# NinjaPCB-4x4-NinNin_ver2_0.net
KiCad netlist of a schematic drawn in EAGLE
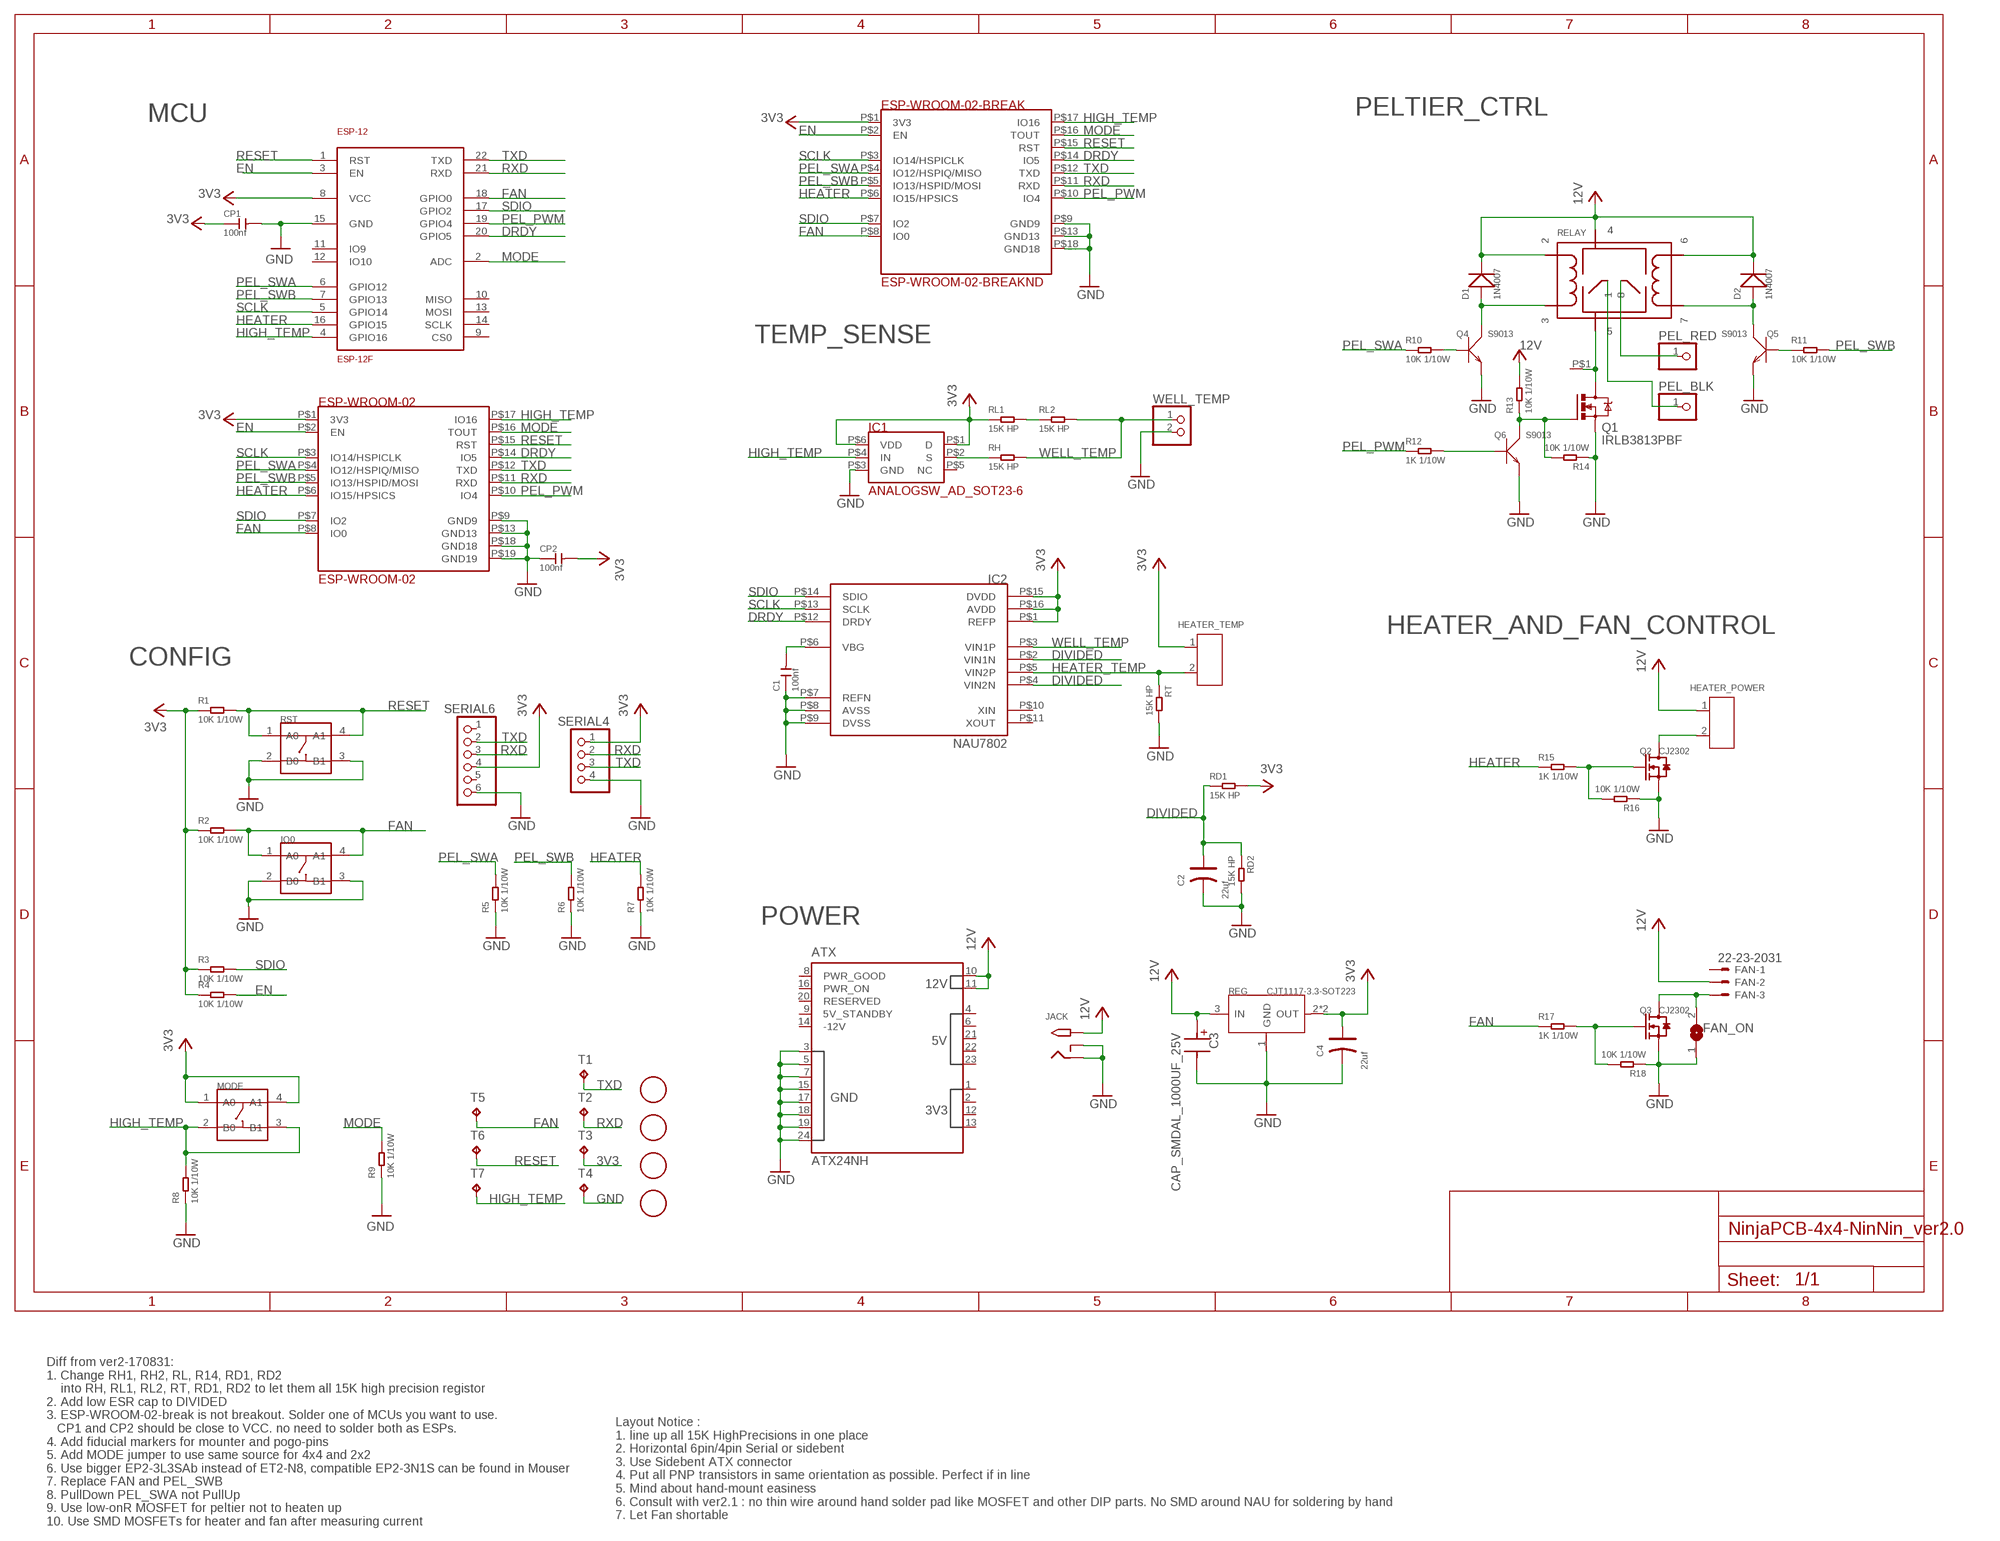
[diagram p0: schematic, sheet 1]

(export (version "E")
  (design (tool "Eeschema 10.0.6"))
  (components
    (comp (ref "ATX")
      (value "ATX24NH")
      (footprint "eagle-import:ATX24")
      (libsource (lib "eagle-import") (part "ATX24NH"))
    )
    (comp (ref "C1")
      (value "100nf")
      (footprint "eagle-import:C0603")
      (fields (field (name "MPN") "CC0603KRX7R9BB104"))
      (libsource (lib "eagle-import") (part "CERAMIC-100NF-50V-10%-X7R(0603)"))
    )
    (comp (ref "C2")
      (value "22uf")
      (footprint "eagle-import:AVX-B")
      (fields (field (name "MPN") "TAJB226*016#NJ"))
      (libsource (lib "eagle-import") (part "TANTALUM-SMD-22UF-16V(AVX-B)"))
    )
    (comp (ref "C3")
      (value "CAP_SMDAL_1000UF_25V")
      (footprint "eagle-import:CAP_SMD_AL_D125")
      (libsource (lib "eagle-import") (part "CAP_SMDAL_1000UF_25V"))
    )
    (comp (ref "C4")
      (value "22uf")
      (footprint "eagle-import:AVX-B")
      (fields (field (name "MPN") "TAJB226*016#NJ"))
      (libsource (lib "eagle-import") (part "TANTALUM-SMD-22UF-16V(AVX-B)"))
    )
    (comp (ref "CP1")
      (value "100nf")
      (footprint "eagle-import:C0603")
      (fields (field (name "MPN") "CC0603KRX7R9BB104"))
      (libsource (lib "eagle-import") (part "CERAMIC-100NF-50V-10%-X7R(0603)"))
    )
    (comp (ref "CP2")
      (value "100nf")
      (footprint "eagle-import:C0603")
      (fields (field (name "MPN") "CC0603KRX7R9BB104"))
      (libsource (lib "eagle-import") (part "CERAMIC-100NF-50V-10%-X7R(0603)"))
    )
    (comp (ref "D1")
      (value "1N4007")
      (footprint "eagle-import:DO-214AC")
      (libsource (lib "eagle-import") (part "DIODE-GEN-PURPOSE-1KV-1A(DO-214AC)"))
    )
    (comp (ref "D2")
      (value "1N4007")
      (footprint "eagle-import:DO-214AC")
      (libsource (lib "eagle-import") (part "DIODE-GEN-PURPOSE-1KV-1A(DO-214AC)"))
    )
    (comp (ref "ESP-12")
      (value "ESP-12F")
      (footprint "eagle-import:ESP-12F")
      (libsource (lib "eagle-import") (part "ESP-12F"))
    )
    (comp (ref "ESP-WROOM-02")
      (value "ESP-WROOM-02")
      (footprint "eagle-import:ESP-WROOM-02")
      (libsource (lib "eagle-import") (part "ESP-WROOM-02"))
    )
    (comp (ref "ESP-WROOM-02-BREAK")
      (value "ESP-WROOM-02-BREAKND")
      (footprint "eagle-import:ESP-WROOM-02-BREAK-NODETAIL")
      (libsource (lib "eagle-import") (part "ESP-WROOM-02-BREAKND"))
    )
    (comp (ref "FAN")
      (value "22-23-2031")
      (footprint "eagle-import:22-23-2031")
      (fields (field (name "MF") "MOLEX"))
      (libsource (lib "eagle-import") (part "22-23-2031"))
    )
    (comp (ref "FAN_ON")
      (value "SJ")
      (footprint "eagle-import:SJ")
      (libsource (lib "eagle-import") (part "SJ"))
    )
    (comp (ref "HEATER_POWER")
      (value "SCREW-TERMINAL-GREEN(2P-3.5)")
      (footprint "eagle-import:H2-3.5-7.0X7.0MM")
      (libsource (lib "eagle-import") (part "SCREW-TERMINAL-GREEN(2P-3.5)"))
    )
    (comp (ref "HEATER_TEMP")
      (value "SCREW-TERMINAL-GREEN(2P-3.5)")
      (footprint "eagle-import:H2-3.5-7.0X7.0MM")
      (libsource (lib "eagle-import") (part "SCREW-TERMINAL-GREEN(2P-3.5)"))
    )
    (comp (ref "HEATSINK")
      (value "HEAT111PB015")
      (footprint "eagle-import:HEAT11PB015")
      (libsource (lib "eagle-import") (part "HEAT111PB015"))
    )
    (comp (ref "IC1")
      (value "ANALOGSW_AD_SOT23-6")
      (footprint "eagle-import:SOT-23-6")
      (libsource (lib "eagle-import") (part "ANALOGSW_AD_SOT23-6"))
    )
    (comp (ref "IC2")
      (value "NAU7802")
      (footprint "eagle-import:SOP-16")
      (libsource (lib "eagle-import") (part "NAU7802"))
    )
    (comp (ref "IO0")
      (value "DIP-SWITCH-TACTILE-SPST-NO/TS-1109(4P-D6.0MM)'TS-1109'")
      (footprint "eagle-import:SW4-6.0X6.0X5.0MM")
      (libsource (lib "eagle-import") (part "DIP-SWITCH-TACTILE-SPST-NO/TS-1109(4P-D6.0MM)'TS-1109'"))
    )
    (comp (ref "JACK")
      (value "2.1MMJACKTHM")
      (footprint "eagle-import:PJ-102A")
      (libsource (lib "eagle-import") (part "2.1MMJACKTHM"))
    )
    (comp (ref "MODE")
      (value "DIP-SWITCH-TACTILE-SPST-NO/TS-1109(4P-D6.0MM)'TS-1109'")
      (footprint "eagle-import:SW4-6.0X6.0X5.0MM")
      (libsource (lib "eagle-import") (part "DIP-SWITCH-TACTILE-SPST-NO/TS-1109(4P-D6.0MM)'TS-1109'"))
    )
    (comp (ref "PEL_BLK")
      (value "PINHD-1X1L")
      (footprint "eagle-import:1X01LONG")
      (libsource (lib "eagle-import") (part "PINHD-1X1L"))
    )
    (comp (ref "PEL_RED")
      (value "PINHD-1X1L")
      (footprint "eagle-import:1X01LONG")
      (libsource (lib "eagle-import") (part "PINHD-1X1L"))
    )
    (comp (ref "Q1")
      (value "IRLB3813PBF")
      (footprint "eagle-import:TO220BV")
      (libsource (lib "eagle-import") (part "IRF520"))
    )
    (comp (ref "Q2")
      (value "CJ2302")
      (footprint "eagle-import:SOT-23")
      (libsource (lib "eagle-import") (part "SMD-MOSFET-N-CH-20V-2.1A-CJ2302(SOT-23)"))
    )
    (comp (ref "Q3")
      (value "CJ2302")
      (footprint "eagle-import:SOT-23")
      (libsource (lib "eagle-import") (part "SMD-MOSFET-N-CH-20V-2.1A-CJ2302(SOT-23)"))
    )
    (comp (ref "Q4")
      (value "S9013")
      (footprint "eagle-import:SOT-23")
      (libsource (lib "eagle-import") (part "SMD-TRANSISTORS-NPN-25V-500MA-S9013(SOT-23)"))
    )
    (comp (ref "Q5")
      (value "S9013")
      (footprint "eagle-import:SOT-23")
      (libsource (lib "eagle-import") (part "SMD-TRANSISTORS-NPN-25V-500MA-S9013(SOT-23)"))
    )
    (comp (ref "Q6")
      (value "S9013")
      (footprint "eagle-import:SOT-23")
      (libsource (lib "eagle-import") (part "SMD-TRANSISTORS-NPN-25V-500MA-S9013(SOT-23)"))
    )
    (comp (ref "R1")
      (value "10K 1/10W")
      (footprint "eagle-import:R0603")
      (fields (field (name "MPN") "RC0603JR-0710KL"))
      (libsource (lib "eagle-import") (part "SMD-RES-10K-5%-1/10W(0603)"))
    )
    (comp (ref "R2")
      (value "10K 1/10W")
      (footprint "eagle-import:R0603")
      (fields (field (name "MPN") "RC0603JR-0710KL"))
      (libsource (lib "eagle-import") (part "SMD-RES-10K-5%-1/10W(0603)"))
    )
    (comp (ref "R3")
      (value "10K 1/10W")
      (footprint "eagle-import:R0603")
      (fields (field (name "MPN") "RC0603JR-0710KL"))
      (libsource (lib "eagle-import") (part "SMD-RES-10K-5%-1/10W(0603)"))
    )
    (comp (ref "R4")
      (value "10K 1/10W")
      (footprint "eagle-import:R0603")
      (fields (field (name "MPN") "RC0603JR-0710KL"))
      (libsource (lib "eagle-import") (part "SMD-RES-10K-5%-1/10W(0603)"))
    )
    (comp (ref "R5")
      (value "10K 1/10W")
      (footprint "eagle-import:R0603")
      (fields (field (name "MPN") "RC0603JR-0710KL"))
      (libsource (lib "eagle-import") (part "SMD-RES-10K-5%-1/10W(0603)"))
    )
    (comp (ref "R6")
      (value "10K 1/10W")
      (footprint "eagle-import:R0603")
      (fields (field (name "MPN") "RC0603JR-0710KL"))
      (libsource (lib "eagle-import") (part "SMD-RES-10K-5%-1/10W(0603)"))
    )
    (comp (ref "R7")
      (value "10K 1/10W")
      (footprint "eagle-import:R0603")
      (fields (field (name "MPN") "RC0603JR-0710KL"))
      (libsource (lib "eagle-import") (part "SMD-RES-10K-5%-1/10W(0603)"))
    )
    (comp (ref "R8")
      (value "10K 1/10W")
      (footprint "eagle-import:R0603")
      (fields (field (name "MPN") "RC0603JR-0710KL"))
      (libsource (lib "eagle-import") (part "SMD-RES-10K-5%-1/10W(0603)"))
    )
    (comp (ref "R9")
      (value "10K 1/10W")
      (footprint "eagle-import:R0603")
      (fields (field (name "MPN") "RC0603JR-0710KL"))
      (libsource (lib "eagle-import") (part "SMD-RES-10K-5%-1/10W(0603)"))
    )
    (comp (ref "R10")
      (value "10K 1/10W")
      (footprint "eagle-import:R0603")
      (fields (field (name "MPN") "RC0603JR-0710KL"))
      (libsource (lib "eagle-import") (part "SMD-RES-10K-5%-1/10W(0603)"))
    )
    (comp (ref "R11")
      (value "10K 1/10W")
      (footprint "eagle-import:R0603")
      (fields (field (name "MPN") "RC0603JR-0710KL"))
      (libsource (lib "eagle-import") (part "SMD-RES-10K-5%-1/10W(0603)"))
    )
    (comp (ref "R12")
      (value "1K 1/10W")
      (footprint "eagle-import:R0603")
      (fields (field (name "MPN") "RC0603JR-071KL"))
      (libsource (lib "eagle-import") (part "SMD-RES-1K-5%-1/10W(0603)"))
    )
    (comp (ref "R13")
      (value "10K 1/10W")
      (footprint "eagle-import:R0603")
      (fields (field (name "MPN") "RC0603JR-0710KL"))
      (libsource (lib "eagle-import") (part "SMD-RES-10K-5%-1/10W(0603)"))
    )
    (comp (ref "R14")
      (value "10K 1/10W")
      (footprint "eagle-import:R0603")
      (fields (field (name "MPN") "RC0603JR-0710KL"))
      (libsource (lib "eagle-import") (part "SMD-RES-10K-5%-1/10W(0603)"))
    )
    (comp (ref "R15")
      (value "1K 1/10W")
      (footprint "eagle-import:R0603")
      (fields (field (name "MPN") "RC0603JR-071KL"))
      (libsource (lib "eagle-import") (part "SMD-RES-1K-5%-1/10W(0603)"))
    )
    (comp (ref "R16")
      (value "10K 1/10W")
      (footprint "eagle-import:R0603")
      (fields (field (name "MPN") "RC0603JR-0710KL"))
      (libsource (lib "eagle-import") (part "SMD-RES-10K-5%-1/10W(0603)"))
    )
    (comp (ref "R17")
      (value "1K 1/10W")
      (footprint "eagle-import:R0603")
      (fields (field (name "MPN") "RC0603JR-071KL"))
      (libsource (lib "eagle-import") (part "SMD-RES-1K-5%-1/10W(0603)"))
    )
    (comp (ref "R18")
      (value "10K 1/10W")
      (footprint "eagle-import:R0603")
      (fields (field (name "MPN") "RC0603JR-0710KL"))
      (libsource (lib "eagle-import") (part "SMD-RES-10K-5%-1/10W(0603)"))
    )
    (comp (ref "RD1")
      (value "15K HP")
      (footprint "eagle-import:R0603")
      (libsource (lib "eagle-import") (part "R0603"))
    )
    (comp (ref "RD2")
      (value "15K HP")
      (footprint "eagle-import:R0603")
      (libsource (lib "eagle-import") (part "R0603"))
    )
    (comp (ref "REG")
      (value "CJT1117-3.3-SOT223")
      (footprint "eagle-import:SOT-223")
      (fields (field (name "MPN") "CJT1117-3.3"))
      (libsource (lib "eagle-import") (part "PMIC-CJT1117-3.3(SOT223)"))
    )
    (comp (ref "RELAY")
      (value "NEC-RELAY2EP2")
      (footprint "eagle-import:NEC-EP2")
      (libsource (lib "eagle-import") (part "NEC-RELAY2EP2"))
    )
    (comp (ref "RH")
      (value "15K HP")
      (footprint "eagle-import:R0603")
      (libsource (lib "eagle-import") (part "R0603"))
    )
    (comp (ref "RL1")
      (value "15K HP")
      (footprint "eagle-import:R0603")
      (libsource (lib "eagle-import") (part "R0603"))
    )
    (comp (ref "RL2")
      (value "15K HP")
      (footprint "eagle-import:R0603")
      (libsource (lib "eagle-import") (part "R0603"))
    )
    (comp (ref "RST")
      (value "DIP-SWITCH-TACTILE-SPST-NO/TS-1109(4P-D6.0MM)'TS-1109'")
      (footprint "eagle-import:SW4-6.0X6.0X5.0MM")
      (libsource (lib "eagle-import") (part "DIP-SWITCH-TACTILE-SPST-NO/TS-1109(4P-D6.0MM)'TS-1109'"))
    )
    (comp (ref "RT")
      (value "15K HP")
      (footprint "eagle-import:R0603")
      (fields (field (name "MPN") "RC0603FR-072KL"))
      (libsource (lib "eagle-import") (part "SMD-RES-2K-1%-1/10W(0603)"))
    )
    (comp (ref "SERIAL4")
      (value "PINHD-1X4")
      (footprint "eagle-import:1X04")
      (libsource (lib "eagle-import") (part "PINHD-1X4"))
    )
    (comp (ref "SERIAL6")
      (value "PINHD-1X6")
      (footprint "eagle-import:1X06")
      (libsource (lib "eagle-import") (part "PINHD-1X6"))
    )
    (comp (ref "T1")
      (value "TPTP20R")
      (footprint "eagle-import:TP20R")
      (libsource (lib "eagle-import") (part "TPTP20R"))
    )
    (comp (ref "T2")
      (value "TPTP20R")
      (footprint "eagle-import:TP20R")
      (libsource (lib "eagle-import") (part "TPTP20R"))
    )
    (comp (ref "T3")
      (value "TPTP20R")
      (footprint "eagle-import:TP20R")
      (libsource (lib "eagle-import") (part "TPTP20R"))
    )
    (comp (ref "T4")
      (value "TPTP20R")
      (footprint "eagle-import:TP20R")
      (libsource (lib "eagle-import") (part "TPTP20R"))
    )
    (comp (ref "T5")
      (value "TPTP20R")
      (footprint "eagle-import:TP20R")
      (libsource (lib "eagle-import") (part "TPTP20R"))
    )
    (comp (ref "T6")
      (value "TPTP20R")
      (footprint "eagle-import:TP20R")
      (libsource (lib "eagle-import") (part "TPTP20R"))
    )
    (comp (ref "T7")
      (value "TPTP20R")
      (footprint "eagle-import:TP20R")
      (libsource (lib "eagle-import") (part "TPTP20R"))
    )
    (comp (ref "U$3")
      (value "FIDUCIAL")
      (footprint "eagle-import:FIDUCIAL_1MM")
      (libsource (lib "eagle-import") (part "FIDUCIAL"))
    )
    (comp (ref "U$4")
      (value "FIDUCIAL")
      (footprint "eagle-import:FIDUCIAL_1MM")
      (libsource (lib "eagle-import") (part "FIDUCIAL"))
    )
    (comp (ref "U$5")
      (value "FIDUCIAL")
      (footprint "eagle-import:FIDUCIAL_1MM")
      (libsource (lib "eagle-import") (part "FIDUCIAL"))
    )
    (comp (ref "U$6")
      (value "FIDUCIAL")
      (footprint "eagle-import:FIDUCIAL_1MM")
      (libsource (lib "eagle-import") (part "FIDUCIAL"))
    )
    (comp (ref "WELL_TEMP")
      (value "PINHD-1X2")
      (footprint "eagle-import:1X02")
      (libsource (lib "eagle-import") (part "PINHD-1X2"))
    )
  )
  (nets
    (net (code "1") (name "/DIVIDED") (class "Default")
      (node (ref "C2") (pin "+") (pinfunction "+_+") (pintype "passive"))
      (node (ref "IC2") (pin "P$2") (pinfunction "VIN1N_P$2") (pintype "bidirectional"))
      (node (ref "IC2") (pin "P$4") (pinfunction "VIN2N_P$4") (pintype "bidirectional"))
      (node (ref "RD1") (pin "1") (pinfunction "1_1") (pintype "passive"))
      (node (ref "RD2") (pin "1") (pinfunction "1_1") (pintype "passive"))
    )
    (net (code "2") (name "/DRDY") (class "Default")
      (node (ref "ESP-12") (pin "20") (pinfunction "GPIO5_20") (pintype "bidirectional"))
      (node (ref "ESP-WROOM-02") (pin "P$14") (pinfunction "IO5_P$14") (pintype "bidirectional"))
      (node (ref "ESP-WROOM-02-BREAK") (pin "P$14") (pinfunction "IO5_P$14") (pintype "bidirectional"))
      (node (ref "IC2") (pin "P$12") (pinfunction "DRDY_P$12") (pintype "bidirectional"))
    )
    (net (code "3") (name "/EN") (class "Default")
      (node (ref "ESP-12") (pin "3") (pinfunction "EN_3") (pintype "bidirectional"))
      (node (ref "ESP-WROOM-02") (pin "P$2") (pinfunction "EN_P$2") (pintype "bidirectional"))
      (node (ref "ESP-WROOM-02-BREAK") (pin "P$2") (pinfunction "EN_P$2") (pintype "bidirectional"))
      (node (ref "R4") (pin "2") (pinfunction "2_2") (pintype "passive"))
    )
    (net (code "4") (name "/FAN") (class "Default")
      (node (ref "ESP-12") (pin "18") (pinfunction "GPIO0_18") (pintype "bidirectional"))
      (node (ref "ESP-WROOM-02") (pin "P$8") (pinfunction "IO0_P$8") (pintype "bidirectional"))
      (node (ref "ESP-WROOM-02-BREAK") (pin "P$8") (pinfunction "IO0_P$8") (pintype "bidirectional"))
      (node (ref "IO0") (pin "1") (pinfunction "A0_1") (pintype "bidirectional"))
      (node (ref "IO0") (pin "4") (pinfunction "A1_4") (pintype "bidirectional"))
      (node (ref "R17") (pin "1") (pinfunction "1_1") (pintype "passive"))
      (node (ref "R2") (pin "2") (pinfunction "2_2") (pintype "passive"))
      (node (ref "T5") (pin "TP") (pinfunction "TP_TP") (pintype "input"))
    )
    (net (code "5") (name "/HEATER") (class "Default")
      (node (ref "ESP-12") (pin "16") (pinfunction "GPIO15_16") (pintype "bidirectional"))
      (node (ref "ESP-WROOM-02") (pin "P$6") (pinfunction "IO15/HPSICS_P$6") (pintype "bidirectional"))
      (node (ref "ESP-WROOM-02-BREAK") (pin "P$6") (pinfunction "IO15/HPSICS_P$6") (pintype "bidirectional"))
      (node (ref "R15") (pin "1") (pinfunction "1_1") (pintype "passive"))
      (node (ref "R7") (pin "2") (pinfunction "2_2") (pintype "passive"))
    )
    (net (code "6") (name "/HEATER_TEMP") (class "Default")
      (node (ref "HEATER_TEMP") (pin "2") (pinfunction "2_2") (pintype "bidirectional"))
      (node (ref "IC2") (pin "P$5") (pinfunction "VIN2P_P$5") (pintype "bidirectional"))
      (node (ref "RT") (pin "1") (pinfunction "1_1") (pintype "passive"))
    )
    (net (code "7") (name "/HIGH_TEMP") (class "Default")
      (node (ref "ESP-12") (pin "4") (pinfunction "GPIO16_4") (pintype "bidirectional"))
      (node (ref "ESP-WROOM-02") (pin "P$17") (pinfunction "IO16_P$17") (pintype "bidirectional"))
      (node (ref "ESP-WROOM-02-BREAK") (pin "P$17") (pinfunction "IO16_P$17") (pintype "bidirectional"))
      (node (ref "IC1") (pin "P$4") (pinfunction "IN_P$4") (pintype "bidirectional"))
      (node (ref "MODE") (pin "2") (pinfunction "B0_2") (pintype "bidirectional"))
      (node (ref "MODE") (pin "3") (pinfunction "B1_3") (pintype "bidirectional"))
      (node (ref "R8") (pin "2") (pinfunction "2_2") (pintype "passive"))
      (node (ref "T7") (pin "TP") (pinfunction "TP_TP") (pintype "input"))
    )
    (net (code "8") (name "/MODE") (class "Default")
      (node (ref "ESP-12") (pin "2") (pinfunction "ADC_2") (pintype "bidirectional"))
      (node (ref "ESP-WROOM-02") (pin "P$16") (pinfunction "TOUT_P$16") (pintype "bidirectional"))
      (node (ref "ESP-WROOM-02-BREAK") (pin "P$16") (pinfunction "TOUT_P$16") (pintype "bidirectional"))
      (node (ref "R9") (pin "2") (pinfunction "2_2") (pintype "passive"))
    )
    (net (code "9") (name "/PEL_PWM") (class "Default")
      (node (ref "ESP-12") (pin "19") (pinfunction "GPIO4_19") (pintype "bidirectional"))
      (node (ref "ESP-WROOM-02") (pin "P$10") (pinfunction "IO4_P$10") (pintype "bidirectional"))
      (node (ref "ESP-WROOM-02-BREAK") (pin "P$10") (pinfunction "IO4_P$10") (pintype "bidirectional"))
      (node (ref "R12") (pin "1") (pinfunction "1_1") (pintype "passive"))
    )
    (net (code "10") (name "/PEL_SWA") (class "Default")
      (node (ref "ESP-12") (pin "6") (pinfunction "GPIO12_6") (pintype "bidirectional"))
      (node (ref "ESP-WROOM-02") (pin "P$4") (pinfunction "IO12/HSPIQ/MISO_P$4") (pintype "bidirectional"))
      (node (ref "ESP-WROOM-02-BREAK") (pin "P$4") (pinfunction "IO12/HSPIQ/MISO_P$4") (pintype "bidirectional"))
      (node (ref "R10") (pin "1") (pinfunction "1_1") (pintype "passive"))
      (node (ref "R5") (pin "2") (pinfunction "2_2") (pintype "passive"))
    )
    (net (code "11") (name "/PEL_SWB") (class "Default")
      (node (ref "ESP-12") (pin "7") (pinfunction "GPIO13_7") (pintype "bidirectional"))
      (node (ref "ESP-WROOM-02") (pin "P$5") (pinfunction "IO13/HSPID/MOSI_P$5") (pintype "bidirectional"))
      (node (ref "ESP-WROOM-02-BREAK") (pin "P$5") (pinfunction "IO13/HSPID/MOSI_P$5") (pintype "bidirectional"))
      (node (ref "R11") (pin "2") (pinfunction "2_2") (pintype "passive"))
      (node (ref "R6") (pin "2") (pinfunction "2_2") (pintype "passive"))
    )
    (net (code "12") (name "/RESET") (class "Default")
      (node (ref "ESP-12") (pin "1") (pinfunction "RST_1") (pintype "bidirectional"))
      (node (ref "ESP-WROOM-02") (pin "P$15") (pinfunction "RST_P$15") (pintype "bidirectional"))
      (node (ref "ESP-WROOM-02-BREAK") (pin "P$15") (pinfunction "RST_P$15") (pintype "bidirectional"))
      (node (ref "R1") (pin "2") (pinfunction "2_2") (pintype "passive"))
      (node (ref "RST") (pin "1") (pinfunction "A0_1") (pintype "bidirectional"))
      (node (ref "RST") (pin "4") (pinfunction "A1_4") (pintype "bidirectional"))
      (node (ref "T6") (pin "TP") (pinfunction "TP_TP") (pintype "input"))
    )
    (net (code "13") (name "/RXD") (class "Default")
      (node (ref "ESP-12") (pin "21") (pinfunction "RXD_21") (pintype "bidirectional"))
      (node (ref "ESP-WROOM-02") (pin "P$11") (pinfunction "RXD_P$11") (pintype "bidirectional"))
      (node (ref "ESP-WROOM-02-BREAK") (pin "P$11") (pinfunction "RXD_P$11") (pintype "bidirectional"))
      (node (ref "SERIAL4") (pin "2") (pinfunction "2_2") (pintype "passive"))
      (node (ref "SERIAL6") (pin "3") (pinfunction "3_3") (pintype "passive"))
      (node (ref "T2") (pin "TP") (pinfunction "TP_TP") (pintype "input"))
    )
    (net (code "14") (name "/SCLK") (class "Default")
      (node (ref "ESP-12") (pin "5") (pinfunction "GPIO14_5") (pintype "bidirectional"))
      (node (ref "ESP-WROOM-02") (pin "P$3") (pinfunction "IO14/HSPICLK_P$3") (pintype "bidirectional"))
      (node (ref "ESP-WROOM-02-BREAK") (pin "P$3") (pinfunction "IO14/HSPICLK_P$3") (pintype "bidirectional"))
      (node (ref "IC2") (pin "P$13") (pinfunction "SCLK_P$13") (pintype "bidirectional"))
    )
    (net (code "15") (name "/SDIO") (class "Default")
      (node (ref "ESP-12") (pin "17") (pinfunction "GPIO2_17") (pintype "bidirectional"))
      (node (ref "ESP-WROOM-02") (pin "P$7") (pinfunction "IO2_P$7") (pintype "bidirectional"))
      (node (ref "ESP-WROOM-02-BREAK") (pin "P$7") (pinfunction "IO2_P$7") (pintype "bidirectional"))
      (node (ref "IC2") (pin "P$14") (pinfunction "SDIO_P$14") (pintype "bidirectional"))
      (node (ref "R3") (pin "2") (pinfunction "2_2") (pintype "passive"))
    )
    (net (code "16") (name "/TXD") (class "Default")
      (node (ref "ESP-12") (pin "22") (pinfunction "TXD_22") (pintype "bidirectional"))
      (node (ref "ESP-WROOM-02") (pin "P$12") (pinfunction "TXD_P$12") (pintype "bidirectional"))
      (node (ref "ESP-WROOM-02-BREAK") (pin "P$12") (pinfunction "TXD_P$12") (pintype "bidirectional"))
      (node (ref "SERIAL4") (pin "3") (pinfunction "3_3") (pintype "passive"))
      (node (ref "SERIAL6") (pin "2") (pinfunction "2_2") (pintype "passive"))
      (node (ref "T1") (pin "TP") (pinfunction "TP_TP") (pintype "input"))
    )
    (net (code "17") (name "/WELL_TEMP") (class "Default")
      (node (ref "IC2") (pin "P$3") (pinfunction "VIN1P_P$3") (pintype "bidirectional"))
      (node (ref "RH") (pin "2") (pinfunction "2_2") (pintype "passive"))
      (node (ref "RL2") (pin "2") (pinfunction "2_2") (pintype "passive"))
      (node (ref "WELL_TEMP") (pin "1") (pinfunction "1_1") (pintype "passive"))
    )
    (net (code "18") (name "3V3") (class "Default")
      (node (ref "C4") (pin "+") (pinfunction "+_+") (pintype "passive"))
      (node (ref "CP1") (pin "1") (pinfunction "1_1") (pintype "passive"))
      (node (ref "CP2") (pin "2") (pinfunction "2_2") (pintype "passive"))
      (node (ref "ESP-12") (pin "8") (pinfunction "VCC_8") (pintype "bidirectional"))
      (node (ref "ESP-WROOM-02") (pin "P$1") (pinfunction "3V3_P$1") (pintype "bidirectional"))
      (node (ref "ESP-WROOM-02-BREAK") (pin "P$1") (pinfunction "3V3_P$1") (pintype "bidirectional"))
      (node (ref "HEATER_TEMP") (pin "1") (pinfunction "1_1") (pintype "bidirectional"))
      (node (ref "IC1") (pin "P$1") (pinfunction "D_P$1") (pintype "bidirectional"))
      (node (ref "IC1") (pin "P$6") (pinfunction "VDD_P$6") (pintype "bidirectional"))
      (node (ref "IC2") (pin "P$1") (pinfunction "REFP_P$1") (pintype "bidirectional"))
      (node (ref "IC2") (pin "P$15") (pinfunction "DVDD_P$15") (pintype "bidirectional"))
      (node (ref "IC2") (pin "P$16") (pinfunction "AVDD_P$16") (pintype "bidirectional"))
      (node (ref "MODE") (pin "1") (pinfunction "A0_1") (pintype "bidirectional"))
      (node (ref "MODE") (pin "4") (pinfunction "A1_4") (pintype "bidirectional"))
      (node (ref "R1") (pin "1") (pinfunction "1_1") (pintype "passive"))
      (node (ref "R2") (pin "1") (pinfunction "1_1") (pintype "passive"))
      (node (ref "R3") (pin "1") (pinfunction "1_1") (pintype "passive"))
      (node (ref "R4") (pin "1") (pinfunction "1_1") (pintype "passive"))
      (node (ref "RD1") (pin "2") (pinfunction "2_2") (pintype "passive"))
      (node (ref "REG") (pin "2") (pinfunction "OUT_2") (pintype "bidirectional"))
      (node (ref "REG") (pin "TER") (pinfunction "OUT_TER") (pintype "bidirectional"))
      (node (ref "RL1") (pin "1") (pinfunction "1_1") (pintype "passive"))
      (node (ref "SERIAL4") (pin "1") (pinfunction "1_1") (pintype "passive"))
      (node (ref "SERIAL6") (pin "4") (pinfunction "4_4") (pintype "passive"))
      (node (ref "T3") (pin "TP") (pinfunction "TP_TP") (pintype "input"))
    )
    (net (code "19") (name "12V") (class "Default")
      (node (ref "ATX") (pin "10") (pinfunction "12V_10_10") (pintype "bidirectional"))
      (node (ref "ATX") (pin "11") (pinfunction "12V_11_11") (pintype "bidirectional"))
      (node (ref "C3") (pin "P$P") (pinfunction "P$P_P$P") (pintype "passive"))
      (node (ref "D1") (pin "2") (pinfunction "-_2") (pintype "passive"))
      (node (ref "D2") (pin "2") (pinfunction "-_2") (pintype "passive"))
      (node (ref "FAN") (pin "2") (pinfunction "S_2") (pintype "passive"))
      (node (ref "HEATER_POWER") (pin "1") (pinfunction "1_1") (pintype "bidirectional"))
      (node (ref "JACK") (pin "TIP") (pinfunction "TIP_TIP") (pintype "bidirectional"))
      (node (ref "R13") (pin "2") (pinfunction "2_2") (pintype "passive"))
      (node (ref "REG") (pin "3") (pinfunction "IN_3") (pintype "bidirectional"))
      (node (ref "RELAY") (pin "P$2") (pinfunction "2_P$2") (pintype "bidirectional"))
      (node (ref "RELAY") (pin "P$4") (pinfunction "4_P$4") (pintype "bidirectional"))
      (node (ref "RELAY") (pin "P$6") (pinfunction "6_P$6") (pintype "bidirectional"))
    )
    (net (code "20") (name "GND") (class "Default")
      (node (ref "ATX") (pin "15") (pinfunction "GND15_15") (pintype "bidirectional"))
      (node (ref "ATX") (pin "17") (pinfunction "GND17_17") (pintype "bidirectional"))
      (node (ref "ATX") (pin "18") (pinfunction "GND18_18") (pintype "bidirectional"))
      (node (ref "ATX") (pin "19") (pinfunction "GND19_19") (pintype "bidirectional"))
      (node (ref "ATX") (pin "24") (pinfunction "GND24_24") (pintype "bidirectional"))
      (node (ref "ATX") (pin "3") (pinfunction "GND3_3") (pintype "bidirectional"))
      (node (ref "ATX") (pin "5") (pinfunction "GND5_5") (pintype "bidirectional"))
      (node (ref "ATX") (pin "7") (pinfunction "GND7_7") (pintype "bidirectional"))
      (node (ref "C1") (pin "1") (pinfunction "1_1") (pintype "passive"))
      (node (ref "C2") (pin "-") (pinfunction "-_-") (pintype "passive"))
      (node (ref "C3") (pin "P$M") (pinfunction "P$M_P$M") (pintype "passive"))
      (node (ref "C4") (pin "-") (pinfunction "-_-") (pintype "passive"))
      (node (ref "CP1") (pin "2") (pinfunction "2_2") (pintype "passive"))
      (node (ref "CP2") (pin "1") (pinfunction "1_1") (pintype "passive"))
      (node (ref "ESP-12") (pin "15") (pinfunction "GND_15") (pintype "bidirectional"))
      (node (ref "ESP-WROOM-02") (pin "P$13") (pinfunction "GND13_P$13") (pintype "bidirectional"))
      (node (ref "ESP-WROOM-02") (pin "P$18") (pinfunction "GND18_P$18") (pintype "bidirectional"))
      (node (ref "ESP-WROOM-02") (pin "P$19") (pinfunction "GND19_P$19") (pintype "bidirectional"))
      (node (ref "ESP-WROOM-02") (pin "P$9") (pinfunction "GND9_P$9") (pintype "bidirectional"))
      (node (ref "ESP-WROOM-02-BREAK") (pin "P$13") (pinfunction "GND13_P$13") (pintype "bidirectional"))
      (node (ref "ESP-WROOM-02-BREAK") (pin "P$18") (pinfunction "GND18_P$18") (pintype "bidirectional"))
      (node (ref "ESP-WROOM-02-BREAK") (pin "P$9") (pinfunction "GND9_P$9") (pintype "bidirectional"))
      (node (ref "FAN_ON") (pin "1") (pinfunction "1_1") (pintype "passive"))
      (node (ref "IC1") (pin "P$3") (pinfunction "GND_P$3") (pintype "bidirectional"))
      (node (ref "IC2") (pin "P$7") (pinfunction "REFN_P$7") (pintype "bidirectional"))
      (node (ref "IC2") (pin "P$8") (pinfunction "AVSS_P$8") (pintype "bidirectional"))
      (node (ref "IC2") (pin "P$9") (pinfunction "DVSS_P$9") (pintype "bidirectional"))
      (node (ref "IO0") (pin "2") (pinfunction "B0_2") (pintype "bidirectional"))
      (node (ref "IO0") (pin "3") (pinfunction "B1_3") (pintype "bidirectional"))
      (node (ref "JACK") (pin "RING") (pinfunction "RING_RING") (pintype "bidirectional"))
      (node (ref "JACK") (pin "RING_SW") (pinfunction "RING_SW_RING_SW") (pintype "bidirectional"))
      (node (ref "Q1") (pin "S") (pinfunction "S_S") (pintype "passive"))
      (node (ref "Q2") (pin "2") (pinfunction "S_2") (pintype "passive"))
      (node (ref "Q3") (pin "2") (pinfunction "S_2") (pintype "passive"))
      (node (ref "Q4") (pin "2") (pinfunction "E_2") (pintype "passive"))
      (node (ref "Q5") (pin "2") (pinfunction "E_2") (pintype "passive"))
      (node (ref "Q6") (pin "2") (pinfunction "E_2") (pintype "passive"))
      (node (ref "R14") (pin "1") (pinfunction "1_1") (pintype "passive"))
      (node (ref "R16") (pin "1") (pinfunction "1_1") (pintype "passive"))
      (node (ref "R18") (pin "1") (pinfunction "1_1") (pintype "passive"))
      (node (ref "R5") (pin "1") (pinfunction "1_1") (pintype "passive"))
      (node (ref "R6") (pin "1") (pinfunction "1_1") (pintype "passive"))
      (node (ref "R7") (pin "1") (pinfunction "1_1") (pintype "passive"))
      (node (ref "R8") (pin "1") (pinfunction "1_1") (pintype "passive"))
      (node (ref "R9") (pin "1") (pinfunction "1_1") (pintype "passive"))
      (node (ref "RD2") (pin "2") (pinfunction "2_2") (pintype "passive"))
      (node (ref "REG") (pin "1") (pinfunction "GND_1") (pintype "bidirectional"))
      (node (ref "RST") (pin "2") (pinfunction "B0_2") (pintype "bidirectional"))
      (node (ref "RST") (pin "3") (pinfunction "B1_3") (pintype "bidirectional"))
      (node (ref "RT") (pin "2") (pinfunction "2_2") (pintype "passive"))
      (node (ref "SERIAL4") (pin "4") (pinfunction "4_4") (pintype "passive"))
      (node (ref "SERIAL6") (pin "6") (pinfunction "6_6") (pintype "passive"))
      (node (ref "T4") (pin "TP") (pinfunction "TP_TP") (pintype "input"))
      (node (ref "WELL_TEMP") (pin "2") (pinfunction "2_2") (pintype "passive"))
    )
    (net (code "21") (name "Net-(D1-+)") (class "Default")
      (node (ref "D1") (pin "1") (pinfunction "+_1") (pintype "passive"))
      (node (ref "Q4") (pin "3") (pinfunction "C_3") (pintype "passive"))
      (node (ref "RELAY") (pin "P$3") (pinfunction "3_P$3") (pintype "bidirectional"))
    )
    (net (code "22") (name "Net-(D2-+)") (class "Default")
      (node (ref "D2") (pin "1") (pinfunction "+_1") (pintype "passive"))
      (node (ref "Q5") (pin "3") (pinfunction "C_3") (pintype "passive"))
      (node (ref "RELAY") (pin "P$7") (pinfunction "7_P$7") (pintype "bidirectional"))
    )
    (net (code "23") (name "Net-(FANC-S)") (class "Default")
      (node (ref "FAN") (pin "3") (pinfunction "S_3") (pintype "passive"))
      (node (ref "FAN_ON") (pin "2") (pinfunction "2_2") (pintype "passive"))
      (node (ref "Q3") (pin "3") (pinfunction "D_3") (pintype "passive"))
    )
    (net (code "24") (name "Net-(IC1-S)") (class "Default")
      (node (ref "IC1") (pin "P$2") (pinfunction "S_P$2") (pintype "bidirectional"))
      (node (ref "RH") (pin "1") (pinfunction "1_1") (pintype "passive"))
    )
    (net (code "25") (name "Net-(IC2-VBG)") (class "Default")
      (node (ref "C1") (pin "2") (pinfunction "2_2") (pintype "passive"))
      (node (ref "IC2") (pin "P$6") (pinfunction "VBG_P$6") (pintype "bidirectional"))
    )
    (net (code "26") (name "Net-(Q2-D)") (class "Default")
      (node (ref "HEATER_POWER") (pin "2") (pinfunction "2_2") (pintype "bidirectional"))
      (node (ref "Q2") (pin "3") (pinfunction "D_3") (pintype "passive"))
    )
    (net (code "27") (name "Net-(Q2-G)") (class "Default")
      (node (ref "Q2") (pin "1") (pinfunction "G_1") (pintype "passive"))
      (node (ref "R15") (pin "2") (pinfunction "2_2") (pintype "passive"))
      (node (ref "R16") (pin "2") (pinfunction "2_2") (pintype "passive"))
    )
    (net (code "28") (name "Net-(Q3-G)") (class "Default")
      (node (ref "Q3") (pin "1") (pinfunction "G_1") (pintype "passive"))
      (node (ref "R17") (pin "2") (pinfunction "2_2") (pintype "passive"))
      (node (ref "R18") (pin "2") (pinfunction "2_2") (pintype "passive"))
    )
    (net (code "29") (name "Net-(Q4-B)") (class "Default")
      (node (ref "Q4") (pin "1") (pinfunction "B_1") (pintype "passive"))
      (node (ref "R10") (pin "2") (pinfunction "2_2") (pintype "passive"))
    )
    (net (code "30") (name "Net-(Q5-B)") (class "Default")
      (node (ref "Q5") (pin "1") (pinfunction "B_1") (pintype "passive"))
      (node (ref "R11") (pin "1") (pinfunction "1_1") (pintype "passive"))
    )
    (net (code "31") (name "Net-(Q6-B)") (class "Default")
      (node (ref "Q6") (pin "1") (pinfunction "B_1") (pintype "passive"))
      (node (ref "R12") (pin "2") (pinfunction "2_2") (pintype "passive"))
    )
    (net (code "32") (name "Net-(Q6-C)") (class "Default")
      (node (ref "Q1") (pin "G") (pinfunction "G_G") (pintype "passive"))
      (node (ref "Q6") (pin "3") (pinfunction "C_3") (pintype "passive"))
      (node (ref "R13") (pin "1") (pinfunction "1_1") (pintype "passive"))
      (node (ref "R14") (pin "2") (pinfunction "2_2") (pintype "passive"))
    )
    (net (code "33") (name "Net-(RELAY-1)") (class "Default")
      (node (ref "PEL_BLK") (pin "1") (pinfunction "1_1") (pintype "passive"))
      (node (ref "RELAY") (pin "P$1") (pinfunction "1_P$1") (pintype "bidirectional"))
    )
    (net (code "34") (name "Net-(RELAY-5)") (class "Default")
      (node (ref "HEATSINK") (pin "P$1") (pinfunction "P$1_P$1") (pintype "bidirectional"))
      (node (ref "Q1") (pin "D") (pinfunction "D_D") (pintype "passive"))
      (node (ref "RELAY") (pin "P$5") (pinfunction "5_P$5") (pintype "bidirectional"))
    )
    (net (code "35") (name "Net-(RELAY-8)") (class "Default")
      (node (ref "PEL_RED") (pin "1") (pinfunction "1_1") (pintype "passive"))
      (node (ref "RELAY") (pin "P$8") (pinfunction "8_P$8") (pintype "bidirectional"))
    )
    (net (code "36") (name "Net-(RL1-Pad2)") (class "Default")
      (node (ref "RL1") (pin "2") (pinfunction "2_2") (pintype "passive"))
      (node (ref "RL2") (pin "1") (pinfunction "1_1") (pintype "passive"))
    )
    (net (code "37") (name "unconnected-(ATX--12V-Pad14)") (class "Default")
      (node (ref "ATX") (pin "14") (pinfunction "-12V_14") (pintype "bidirectional"))
    )
    (net (code "38") (name "unconnected-(ATX-3V3_1-Pad1)") (class "Default")
      (node (ref "ATX") (pin "1") (pinfunction "3V3_1_1") (pintype "bidirectional"))
    )
    (net (code "39") (name "unconnected-(ATX-3V3_2-Pad2)") (class "Default")
      (node (ref "ATX") (pin "2") (pinfunction "3V3_2_2") (pintype "bidirectional"))
    )
    (net (code "40") (name "unconnected-(ATX-3V3_12-Pad12)") (class "Default")
      (node (ref "ATX") (pin "12") (pinfunction "3V3_12_12") (pintype "bidirectional"))
    )
    (net (code "41") (name "unconnected-(ATX-3V3_13-Pad13)") (class "Default")
      (node (ref "ATX") (pin "13") (pinfunction "3V3_13_13") (pintype "bidirectional"))
    )
    (net (code "42") (name "unconnected-(ATX-5V_4-Pad4)") (class "Default")
      (node (ref "ATX") (pin "4") (pinfunction "5V_4_4") (pintype "bidirectional"))
    )
    (net (code "43") (name "unconnected-(ATX-5V_6-Pad6)") (class "Default")
      (node (ref "ATX") (pin "6") (pinfunction "5V_6_6") (pintype "bidirectional"))
    )
    (net (code "44") (name "unconnected-(ATX-5V_21-Pad21)") (class "Default")
      (node (ref "ATX") (pin "21") (pinfunction "5V_21_21") (pintype "bidirectional"))
    )
    (net (code "45") (name "unconnected-(ATX-5V_22-Pad22)") (class "Default")
      (node (ref "ATX") (pin "22") (pinfunction "5V_22_22") (pintype "bidirectional"))
    )
    (net (code "46") (name "unconnected-(ATX-5V_23-Pad23)") (class "Default")
      (node (ref "ATX") (pin "23") (pinfunction "5V_23_23") (pintype "bidirectional"))
    )
    (net (code "47") (name "unconnected-(ATX-5V_STANDBY-Pad9)") (class "Default")
      (node (ref "ATX") (pin "9") (pinfunction "5V_STANDBY_9") (pintype "bidirectional"))
    )
    (net (code "48") (name "unconnected-(ATX-PWR_GOOD-Pad8)") (class "Default")
      (node (ref "ATX") (pin "8") (pinfunction "PWR_GOOD_8") (pintype "bidirectional"))
    )
    (net (code "49") (name "unconnected-(ATX-PWR_ON-Pad16)") (class "Default")
      (node (ref "ATX") (pin "16") (pinfunction "PWR_ON_16") (pintype "bidirectional"))
    )
    (net (code "50") (name "unconnected-(ATX-RESERVED-Pad20)") (class "Default")
      (node (ref "ATX") (pin "20") (pinfunction "RESERVED_20") (pintype "bidirectional"))
    )
    (net (code "51") (name "unconnected-(ESP-12-CS0-Pad9)") (class "Default")
      (node (ref "ESP-12") (pin "9") (pinfunction "CS0_9") (pintype "bidirectional"))
    )
    (net (code "52") (name "unconnected-(ESP-12-IO9-Pad11)") (class "Default")
      (node (ref "ESP-12") (pin "11") (pinfunction "IO9_11") (pintype "bidirectional"))
    )
    (net (code "53") (name "unconnected-(ESP-12-IO10-Pad12)") (class "Default")
      (node (ref "ESP-12") (pin "12") (pinfunction "IO10_12") (pintype "bidirectional"))
    )
    (net (code "54") (name "unconnected-(ESP-12-MISO-Pad10)") (class "Default")
      (node (ref "ESP-12") (pin "10") (pinfunction "MISO_10") (pintype "bidirectional"))
    )
    (net (code "55") (name "unconnected-(ESP-12-MOSI-Pad13)") (class "Default")
      (node (ref "ESP-12") (pin "13") (pinfunction "MOSI_13") (pintype "bidirectional"))
    )
    (net (code "56") (name "unconnected-(ESP-12-SCLK-Pad14)") (class "Default")
      (node (ref "ESP-12") (pin "14") (pinfunction "SCLK_14") (pintype "bidirectional"))
    )
    (net (code "57") (name "unconnected-(FANA-S-Pad1)") (class "Default")
      (node (ref "FAN") (pin "1") (pinfunction "S_1") (pintype "passive"))
    )
    (net (code "58") (name "unconnected-(IC1-NC-PadP$5)") (class "Default")
      (node (ref "IC1") (pin "P$5") (pinfunction "NC_P$5") (pintype "bidirectional"))
    )
    (net (code "59") (name "unconnected-(IC2-XIN-PadP$10)") (class "Default")
      (node (ref "IC2") (pin "P$10") (pinfunction "XIN_P$10") (pintype "bidirectional"))
    )
    (net (code "60") (name "unconnected-(IC2-XOUT-PadP$11)") (class "Default")
      (node (ref "IC2") (pin "P$11") (pinfunction "XOUT_P$11") (pintype "bidirectional"))
    )
    (net (code "61") (name "unconnected-(SERIAL6-Pad1)") (class "Default")
      (node (ref "SERIAL6") (pin "1") (pinfunction "1_1") (pintype "passive"))
    )
    (net (code "62") (name "unconnected-(SERIAL6-Pad5)") (class "Default")
      (node (ref "SERIAL6") (pin "5") (pinfunction "5_5") (pintype "passive"))
    )
  )
)
